# SDCard.net
KiCad netlist of a schematic drawn in Altium Designer
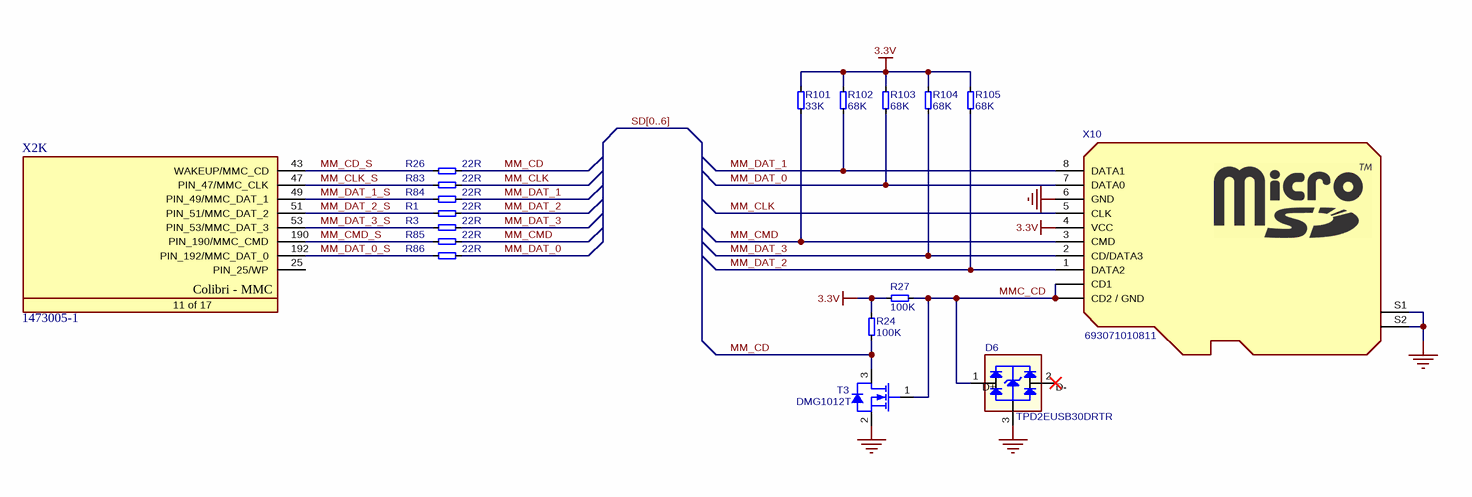
[diagram p0: SDCard.SchDoc]

(export (version "E")
  (design (tool "Eeschema 10.0.6"))
  (components
    (comp (ref "D6")
      (value "TPD2EUSB30DRTR")
      (footprint "T_TI_TPD2EUSB30DRTR")
      (description "2 Channel Protection for Super Speed USB3.0")
      (fields (field (name "MANUFACTURER PART NO.") "TPD2EUSB30DRTR"))
      (libsource (lib "Iris") (part "D-TI-TPD2EUSB30DRTR"))
    )
    (comp (ref "R1")
      (value "22R")
      (footprint "RESC1005X40N")
      (description "Resistor 22 ohm 63mW 5% 0402")
      (fields (field (name "TOLERANCE") "5%"))
      (libsource (lib "Iris") (part "R-22R-63mW-5%-0402"))
    )
    (comp (ref "R3")
      (value "22R")
      (footprint "RESC1005X40N")
      (description "Resistor 22 ohm 63mW 5% 0402")
      (fields (field (name "TOLERANCE") "5%"))
      (libsource (lib "Iris") (part "R-22R-63mW-5%-0402"))
    )
    (comp (ref "R24")
      (value "100K")
      (footprint "T_RESC0603X30N")
      (description "Resistor 100 Kohm 63mW 5% 0603")
      (fields (field (name "TOLERANCE") "5%"))
      (libsource (lib "Iris") (part "R-100KR-63mW-5%-0603"))
    )
    (comp (ref "R26")
      (value "22R")
      (footprint "RESC1005X40N")
      (description "Resistor 22 ohm 63mW 5% 0402")
      (fields (field (name "TOLERANCE") "5%"))
      (libsource (lib "Iris") (part "R-22R-63mW-5%-0402"))
    )
    (comp (ref "R27")
      (value "100K")
      (footprint "T_RESC0603X30N")
      (description "Resistor 100 Kohm 63mW 5% 0603")
      (fields (field (name "TOLERANCE") "5%"))
      (libsource (lib "Iris") (part "R-100KR-63mW-5%-0603"))
    )
    (comp (ref "R83")
      (value "22R")
      (footprint "RESC1005X40N")
      (description "Resistor 22 ohm 63mW 5% 0402")
      (fields (field (name "TOLERANCE") "5%"))
      (libsource (lib "Iris") (part "R-22R-63mW-5%-0402"))
    )
    (comp (ref "R84")
      (value "22R")
      (footprint "RESC1005X40N")
      (description "Resistor 22 ohm 63mW 5% 0402")
      (fields (field (name "TOLERANCE") "5%"))
      (libsource (lib "Iris") (part "R-22R-63mW-5%-0402"))
    )
    (comp (ref "R85")
      (value "22R")
      (footprint "RESC1005X40N")
      (description "Resistor 22 ohm 63mW 5% 0402")
      (fields (field (name "TOLERANCE") "5%"))
      (libsource (lib "Iris") (part "R-22R-63mW-5%-0402"))
    )
    (comp (ref "R86")
      (value "22R")
      (footprint "RESC1005X40N")
      (description "Resistor 22 ohm 63mW 5% 0402")
      (fields (field (name "TOLERANCE") "5%"))
      (libsource (lib "Iris") (part "R-22R-63mW-5%-0402"))
    )
    (comp (ref "R101")
      (value "33K")
      (footprint "RESC1005X40N")
      (description "Resistor 33 Kohm 63mW 5% 0402")
      (fields (field (name "TOLERANCE") "5%"))
      (libsource (lib "Iris") (part "R-33KR-63mW-5%-0402"))
    )
    (comp (ref "R102")
      (value "68K")
      (footprint "RESC1005X40N")
      (description "Resistor 68 Kohm 63mW 5% 0402")
      (fields (field (name "TOLERANCE") "5%"))
      (libsource (lib "Iris") (part "R-68KR-63mW-5%-0402"))
    )
    (comp (ref "R103")
      (value "68K")
      (footprint "RESC1005X40N")
      (description "Resistor 68 Kohm 63mW 5% 0402")
      (fields (field (name "TOLERANCE") "5%"))
      (libsource (lib "Iris") (part "R-68KR-63mW-5%-0402"))
    )
    (comp (ref "R104")
      (value "68K")
      (footprint "RESC1005X40N")
      (description "Resistor 68 Kohm 63mW 5% 0402")
      (fields (field (name "TOLERANCE") "5%"))
      (libsource (lib "Iris") (part "R-68KR-63mW-5%-0402"))
    )
    (comp (ref "R105")
      (value "68K")
      (footprint "RESC1005X40N")
      (description "Resistor 68 Kohm 63mW 5% 0402")
      (fields (field (name "TOLERANCE") "5%"))
      (libsource (lib "Iris") (part "R-68KR-63mW-5%-0402"))
    )
    (comp (ref "T3")
      (value "T-DiodeInc-DMG1012T")
      (footprint "T_SOT50P160X80-3N")
      (description "N-Channel 20V (D-S)  MOSFET")
      (fields (field (name "MANUFACTURER PART NO.") "DMG1012T"))
      (libsource (lib "Iris") (part "T-DiodeInc-DMG1012T"))
    )
    (comp (ref "X2")
      (value "1473005-1")
      (footprint "T_Tyco_1473005-1")
      (description "SODIMM Connector")
      (fields (field (name "MANUFACTURER PART NO.") "1473005-1"))
      (libsource (lib "Iris") (part "CON-Tyco-1473005-1-200-0.6mm"))
    )
    (comp (ref "X10")
      (value "MicroSD Holder")
      (footprint "T_Wurth_693071010811")
      (description "Micro SD Holder Push Push CD")
      (fields (field (name "MANUFACTURER PART NO.") "693071010811"))
      (libsource (lib "Iris") (part "CON-Wurth-693071010811"))
    )
  )
  (nets
    (net (code "8") (name "/MMC_CD") (class "Default")
      (node (ref "D6") (pin "1") (pinfunction "D+_1") (pintype "power_in"))
      (node (ref "R27") (pin "1") (pinfunction "1_1") (pintype "passive"))
      (node (ref "T3") (pin "1") (pinfunction "G_1") (pintype "passive"))
      (node (ref "X10") (pin "CD1") (pinfunction "CD1_CD1") (pintype "power_in"))
      (node (ref "X10") (pin "CD2") (pinfunction "CD2_/_GND_CD2") (pintype "power_in"))
    )
    (net (code "9") (name "/MM_CD") (class "Default")
      (node (ref "R24") (pin "1") (pinfunction "1_1") (pintype "passive"))
      (node (ref "R26") (pin "2") (pinfunction "2_2") (pintype "passive"))
      (node (ref "T3") (pin "3") (pinfunction "D_3") (pintype "passive"))
    )
    (net (code "10") (name "/MM_CD_S") (class "Default")
      (node (ref "R26") (pin "1") (pinfunction "1_1") (pintype "passive"))
      (node (ref "X2") (pin "43") (pinfunction "WAKEUP/MMC_CD_43") (pintype "passive"))
    )
    (net (code "11") (name "/MM_CLK") (class "Default")
      (node (ref "R83") (pin "2") (pinfunction "2_2") (pintype "passive"))
      (node (ref "X10") (pin "5") (pinfunction "CLK_5") (pintype "power_in"))
    )
    (net (code "12") (name "/MM_CLK_S") (class "Default")
      (node (ref "R83") (pin "1") (pinfunction "1_1") (pintype "passive"))
      (node (ref "X2") (pin "47") (pinfunction "PIN_47/MMC_CLK_47") (pintype "passive"))
    )
    (net (code "13") (name "/MM_CMD") (class "Default")
      (node (ref "R101") (pin "1") (pinfunction "1_1") (pintype "passive"))
      (node (ref "R85") (pin "2") (pinfunction "2_2") (pintype "passive"))
      (node (ref "X10") (pin "3") (pinfunction "CMD_3") (pintype "passive"))
    )
    (net (code "14") (name "/MM_CMD_S") (class "Default")
      (node (ref "R85") (pin "1") (pinfunction "1_1") (pintype "passive"))
      (node (ref "X2") (pin "190") (pinfunction "PIN_190/MMC_CMD_190") (pintype "passive"))
    )
    (net (code "15") (name "/MM_DAT_0") (class "Default")
      (node (ref "R103") (pin "1") (pinfunction "1_1") (pintype "passive"))
      (node (ref "R86") (pin "2") (pinfunction "2_2") (pintype "passive"))
      (node (ref "X10") (pin "7") (pinfunction "DATA0_7") (pintype "power_in"))
    )
    (net (code "16") (name "/MM_DAT_0_S") (class "Default")
      (node (ref "R86") (pin "1") (pinfunction "1_1") (pintype "passive"))
      (node (ref "X2") (pin "192") (pinfunction "PIN_192/MMC_DAT_0_192") (pintype "passive"))
    )
    (net (code "17") (name "/MM_DAT_1") (class "Default")
      (node (ref "R102") (pin "1") (pinfunction "1_1") (pintype "passive"))
      (node (ref "R84") (pin "2") (pinfunction "2_2") (pintype "passive"))
      (node (ref "X10") (pin "8") (pinfunction "DATA1_8") (pintype "power_in"))
    )
    (net (code "18") (name "/MM_DAT_1_S") (class "Default")
      (node (ref "R84") (pin "1") (pinfunction "1_1") (pintype "passive"))
      (node (ref "X2") (pin "49") (pinfunction "PIN_49/MMC_DAT_1_49") (pintype "passive"))
    )
    (net (code "19") (name "/MM_DAT_2") (class "Default")
      (node (ref "R1") (pin "2") (pinfunction "2_2") (pintype "passive"))
      (node (ref "R105") (pin "1") (pinfunction "1_1") (pintype "passive"))
      (node (ref "X10") (pin "1") (pinfunction "DATA2_1") (pintype "power_in"))
    )
    (net (code "20") (name "/MM_DAT_2_S") (class "Default")
      (node (ref "R1") (pin "1") (pinfunction "1_1") (pintype "passive"))
      (node (ref "X2") (pin "51") (pinfunction "PIN_51/MMC_DAT_2_51") (pintype "passive"))
    )
    (net (code "21") (name "/MM_DAT_3") (class "Default")
      (node (ref "R104") (pin "1") (pinfunction "1_1") (pintype "passive"))
      (node (ref "R3") (pin "2") (pinfunction "2_2") (pintype "passive"))
      (node (ref "X10") (pin "2") (pinfunction "CD/DATA3_2") (pintype "passive"))
    )
    (net (code "22") (name "/MM_DAT_3_S") (class "Default")
      (node (ref "R3") (pin "1") (pinfunction "1_1") (pintype "passive"))
      (node (ref "X2") (pin "53") (pinfunction "PIN_53/MMC_DAT_3_53") (pintype "passive"))
    )
    (net (code "24") (name "3.3V") (class "Default")
      (node (ref "R101") (pin "2") (pinfunction "2_2") (pintype "passive"))
      (node (ref "R102") (pin "2") (pinfunction "2_2") (pintype "passive"))
      (node (ref "R103") (pin "2") (pinfunction "2_2") (pintype "passive"))
      (node (ref "R104") (pin "2") (pinfunction "2_2") (pintype "passive"))
      (node (ref "R105") (pin "2") (pinfunction "2_2") (pintype "passive"))
      (node (ref "R24") (pin "2") (pinfunction "2_2") (pintype "passive"))
      (node (ref "R27") (pin "2") (pinfunction "2_2") (pintype "passive"))
      (node (ref "X10") (pin "4") (pinfunction "VCC_4") (pintype "passive"))
    )
    (net (code "25") (name "GND") (class "Default")
      (node (ref "D6") (pin "3") (pinfunction "3_3") (pintype "power_in"))
      (node (ref "T3") (pin "2") (pinfunction "S_2") (pintype "passive"))
      (node (ref "X10") (pin "6") (pinfunction "GND_6") (pintype "power_in"))
      (node (ref "X10") (pin "S1") (pinfunction "S_S1") (pintype "passive"))
      (node (ref "X10") (pin "S2") (pinfunction "S_S2") (pintype "passive"))
    )
    (net (code "26") (name "unconnected-(D6-D--Pad2)") (class "Default")
      (node (ref "D6") (pin "2") (pinfunction "D-_2") (pintype "power_in+no_connect"))
    )
    (net (code "27") (name "unconnected-(X2K-PIN_25{slash}WP-Pad25)") (class "Default")
      (node (ref "X2") (pin "25") (pinfunction "PIN_25/WP_25") (pintype "passive"))
    )
  )
)
